# final_schematic.net
KiCad netlist of a schematic drawn in EAGLE
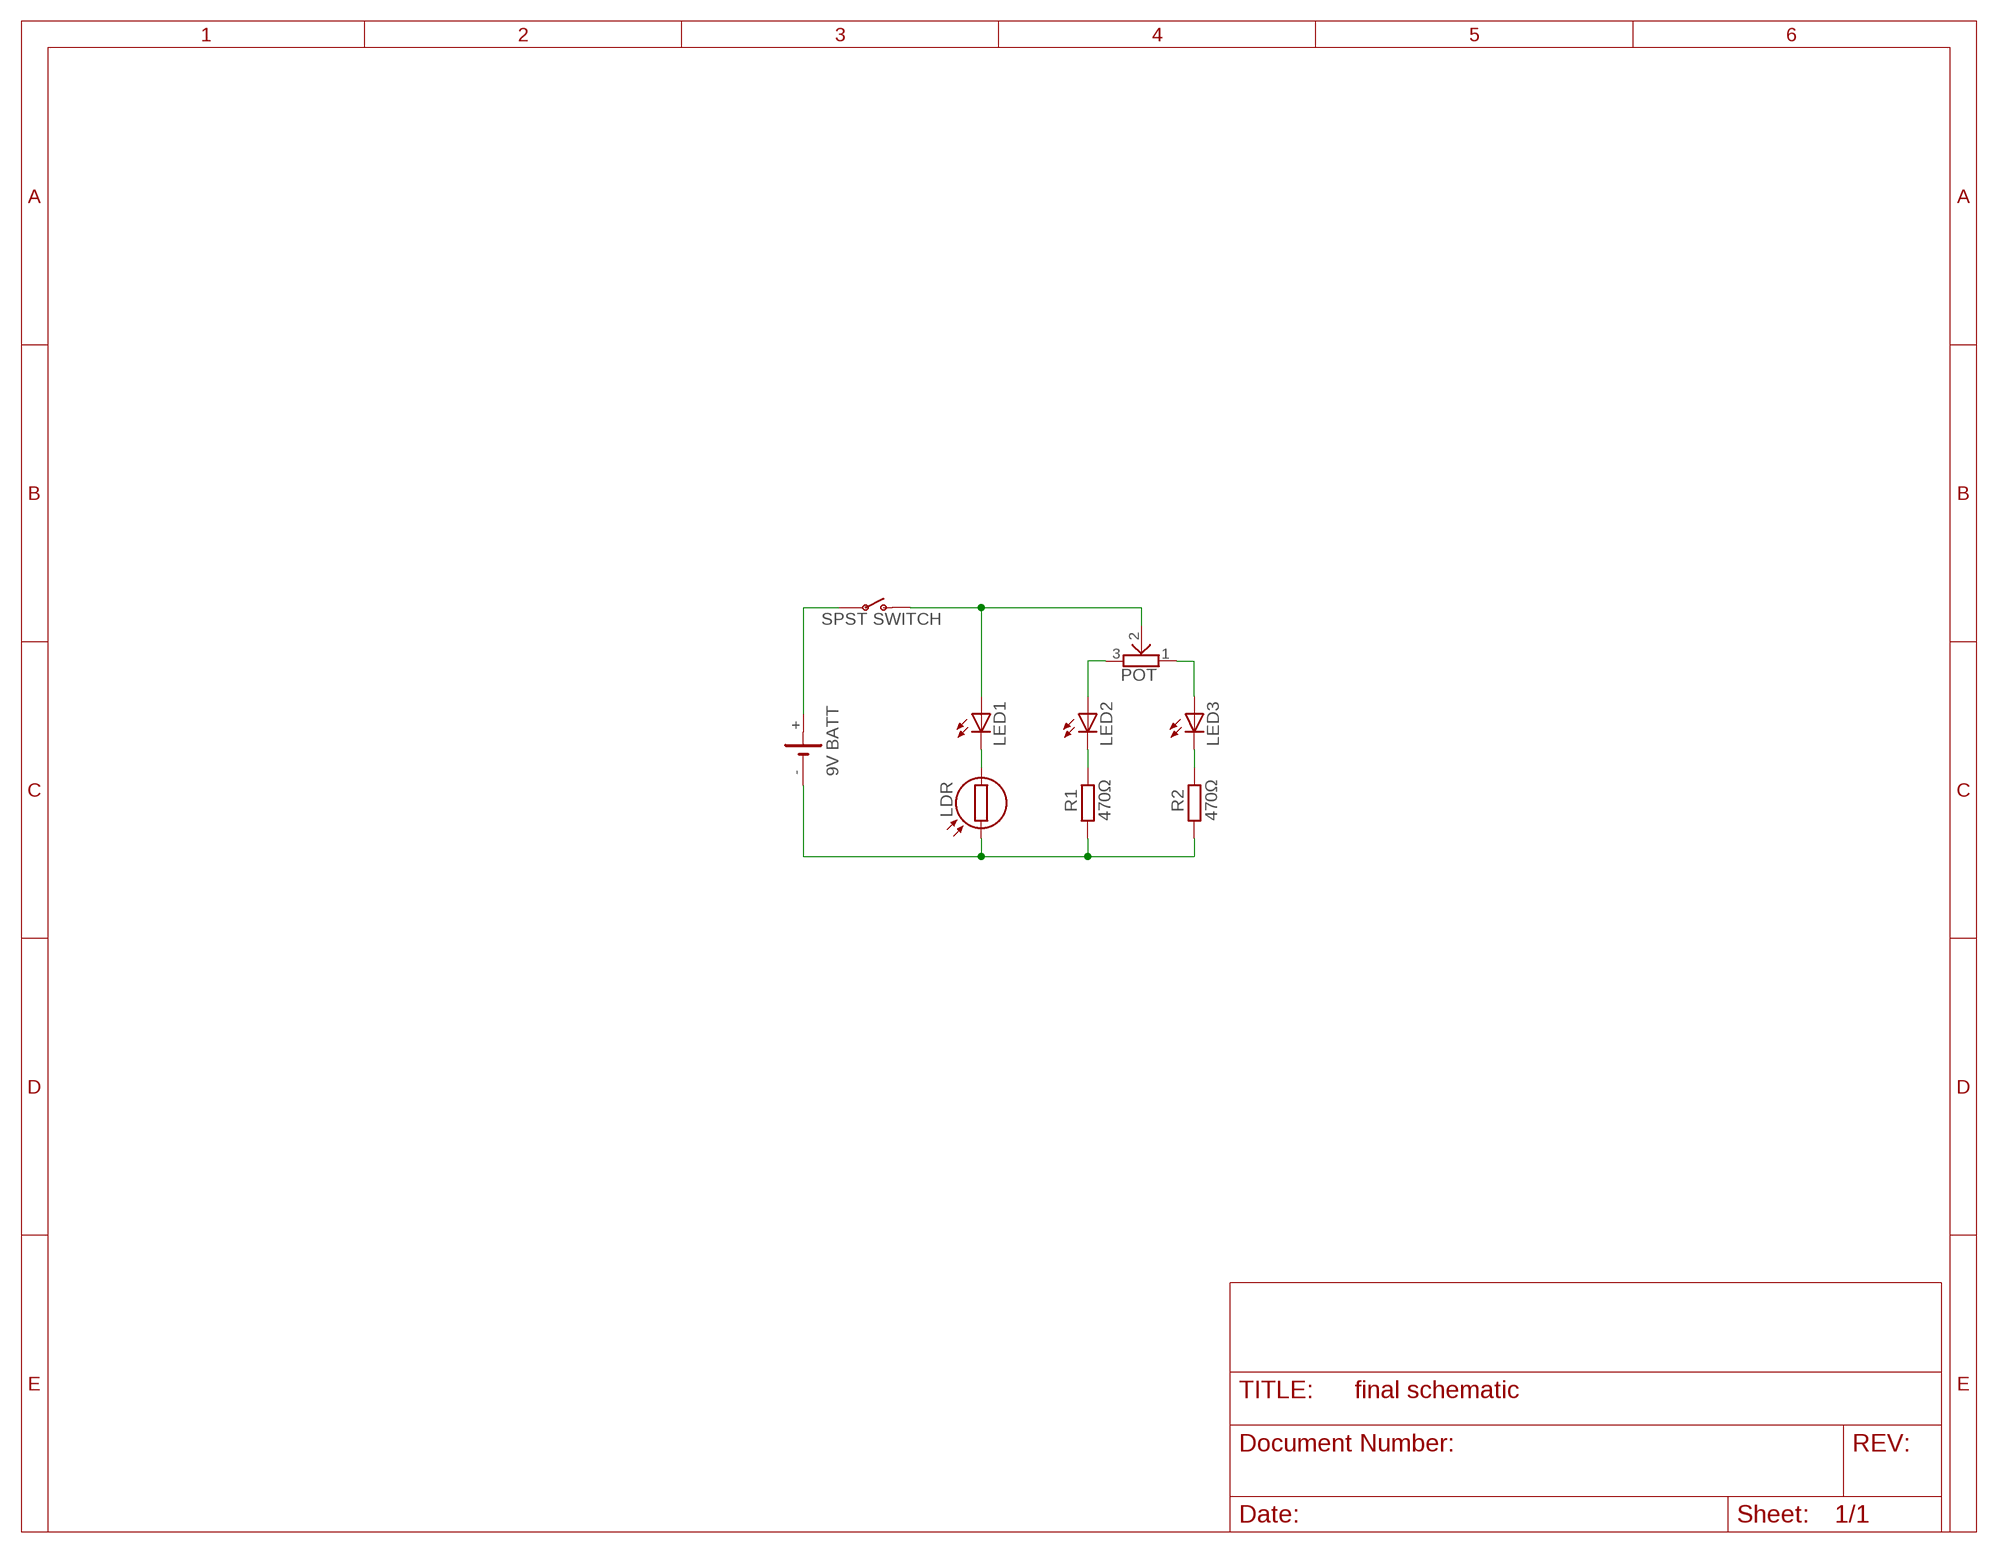
[diagram p0: schematic, sheet 1]

(export (version "E")
  (design (tool "Eeschema 10.0.6"))
  (components
    (comp (ref "G1")
      (value "BATT_9V")
      (footprint "eagle-import:9V_CONNECTOR")
      (libsource (lib "eagle-import") (part "BATT_9V"))
    )
    (comp (ref "LDR")
      (value "LDR_THRU")
      (footprint "eagle-import:LDR")
      (libsource (lib "eagle-import") (part "LDR_THRU"))
    )
    (comp (ref "LED1")
      (value "LED5MM")
      (footprint "eagle-import:LED5MM")
      (libsource (lib "eagle-import") (part "LED5MM"))
    )
    (comp (ref "LED2")
      (value "LED5MM")
      (footprint "eagle-import:LED5MM")
      (libsource (lib "eagle-import") (part "LED5MM"))
    )
    (comp (ref "LED3")
      (value "LED5MM")
      (footprint "eagle-import:LED5MM")
      (libsource (lib "eagle-import") (part "LED5MM"))
    )
    (comp (ref "POT")
      (value "POTENTIOMETER_THRU")
      (footprint "eagle-import:POTENTIOMETER_THRU")
      (libsource (lib "eagle-import") (part "POTENTIOMETER_THRU"))
    )
    (comp (ref "R1")
      (value "470Ω")
      (footprint "eagle-import:0207_10")
      (libsource (lib "eagle-import") (part "R-EU_0207/10"))
    )
    (comp (ref "R2")
      (value "470Ω")
      (footprint "eagle-import:0207_10")
      (libsource (lib "eagle-import") (part "R-EU_0207/10"))
    )
    (comp (ref "U1")
      (value "SWITCH-SPST-2TV")
      (footprint "eagle-import:SWITCH-SPST-VERTICAL")
      (libsource (lib "eagle-import") (part "SWITCH-SPST-2TV"))
    )
  )
  (nets
    (net (code "1") (name "Net-(G1-Pad-)") (class "Default")
      (node (ref "G1") (pin "-") (pinfunction "-_-") (pintype "passive"))
      (node (ref "LDR") (pin "1") (pinfunction "1_1") (pintype "passive"))
      (node (ref "R1") (pin "1") (pinfunction "1_1") (pintype "passive"))
      (node (ref "R2") (pin "1") (pinfunction "1_1") (pintype "passive"))
    )
    (net (code "2") (name "Net-(LED1-C)") (class "Default")
      (node (ref "LDR") (pin "2") (pinfunction "2_2") (pintype "passive"))
      (node (ref "LED1") (pin "K") (pinfunction "C_K") (pintype "passive"))
    )
    (net (code "3") (name "Net-(LED2-C)") (class "Default")
      (node (ref "LED2") (pin "K") (pinfunction "C_K") (pintype "passive"))
      (node (ref "R1") (pin "2") (pinfunction "2_2") (pintype "passive"))
    )
    (net (code "4") (name "Net-(LED2-PadA)") (class "Default")
      (node (ref "LED2") (pin "A") (pinfunction "A_A") (pintype "passive"))
      (node (ref "POT") (pin "3") (pinfunction "3_3") (pintype "passive"))
    )
    (net (code "5") (name "Net-(LED3-C)") (class "Default")
      (node (ref "LED3") (pin "K") (pinfunction "C_K") (pintype "passive"))
      (node (ref "R2") (pin "2") (pinfunction "2_2") (pintype "passive"))
    )
    (net (code "6") (name "Net-(LED3-PadA)") (class "Default")
      (node (ref "LED3") (pin "A") (pinfunction "A_A") (pintype "passive"))
      (node (ref "POT") (pin "1") (pinfunction "1_1") (pintype "passive"))
    )
    (net (code "7") (name "Net-(U1-O)") (class "Default")
      (node (ref "LED1") (pin "A") (pinfunction "A_A") (pintype "passive"))
      (node (ref "POT") (pin "2") (pinfunction "2_2") (pintype "passive"))
      (node (ref "U1") (pin "1") (pinfunction "O_1") (pintype "passive"))
    )
    (net (code "8") (name "Net-(U1-P)") (class "Default")
      (node (ref "G1") (pin "+") (pinfunction "+_+") (pintype "passive"))
      (node (ref "U1") (pin "2") (pinfunction "P_2") (pintype "passive"))
    )
  )
)
